# BBQ_Blower.net
KiCad netlist of a schematic drawn in EAGLE
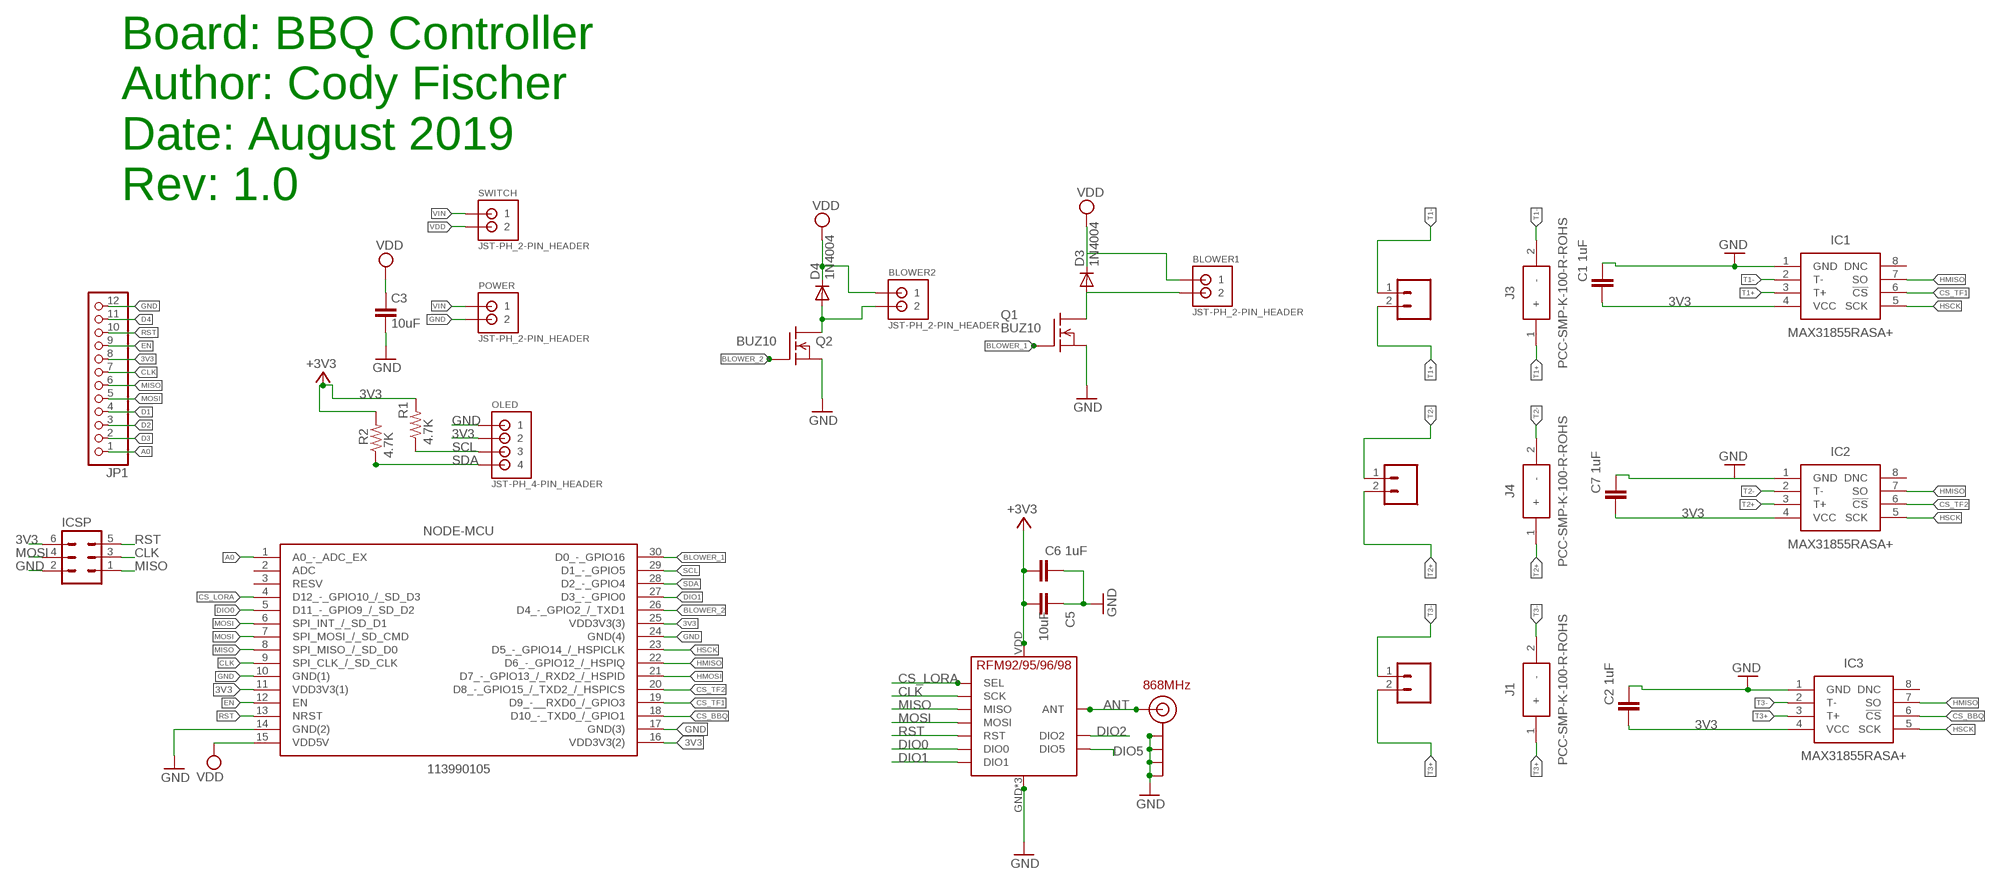
[diagram p0: schematic, sheet 1]

(export (version "E")
  (design (tool "Eeschema 10.0.6"))
  (components
    (comp (ref "BLOWER1")
      (value "JST-PH_2-PIN_HEADER")
      (footprint "eagle-import:JST_B2B-PH_HEADER")
      (libsource (lib "eagle-import") (part "JST-PH_2-PIN_HEADER"))
    )
    (comp (ref "BLOWER2")
      (value "JST-PH_2-PIN_HEADER")
      (footprint "eagle-import:JST_B2B-PH_HEADER")
      (libsource (lib "eagle-import") (part "JST-PH_2-PIN_HEADER"))
    )
    (comp (ref "C1")
      (value "1uF")
      (footprint "eagle-import:C0805K")
      (libsource (lib "eagle-import") (part "C-EUC0805K"))
    )
    (comp (ref "C2")
      (value "1uF")
      (footprint "eagle-import:C0805K")
      (libsource (lib "eagle-import") (part "C-EUC0805K"))
    )
    (comp (ref "C3")
      (value "10uF")
      (footprint "eagle-import:C025-050X050")
      (libsource (lib "eagle-import") (part "C-EU025-050X050"))
    )
    (comp (ref "C5")
      (value "10uF")
      (footprint "eagle-import:C0805K")
      (libsource (lib "eagle-import") (part "C-EUC0805K"))
    )
    (comp (ref "C6")
      (value "1uF")
      (footprint "eagle-import:C0805K")
      (libsource (lib "eagle-import") (part "C-EUC0805K"))
    )
    (comp (ref "C7")
      (value "1uF")
      (footprint "eagle-import:C0805K")
      (libsource (lib "eagle-import") (part "C-EUC0805K"))
    )
    (comp (ref "D3")
      (value "1N4004")
      (footprint "eagle-import:DO41-10")
      (libsource (lib "eagle-import") (part "1N4004"))
    )
    (comp (ref "D4")
      (value "1N4004")
      (footprint "eagle-import:DO41-10")
      (libsource (lib "eagle-import") (part "1N4004"))
    )
    (comp (ref "IC1")
      (value "MAX31855RASA+")
      (footprint "eagle-import:SOIC127P600X175-8N")
      (fields (field (name "RS_PART_NUMBER") "7833891P"))
      (libsource (lib "eagle-import") (part "MAX31855RASA+"))
    )
    (comp (ref "IC2")
      (value "MAX31855RASA+")
      (footprint "eagle-import:SOIC127P600X175-8N")
      (fields (field (name "RS_PART_NUMBER") "7833891P"))
      (libsource (lib "eagle-import") (part "MAX31855RASA+"))
    )
    (comp (ref "IC3")
      (value "MAX31855RASA+")
      (footprint "eagle-import:SOIC127P600X175-8N")
      (fields (field (name "RS_PART_NUMBER") "7833891P"))
      (libsource (lib "eagle-import") (part "MAX31855RASA+"))
    )
    (comp (ref "ICSP")
      (value "MA03-2")
      (footprint "eagle-import:MA03-2")
      (libsource (lib "eagle-import") (part "MA03-2"))
    )
    (comp (ref "J$2")
      (value "ANTENNATINY")
      (footprint "eagle-import:SMA_UFL_PAD_TINY")
      (libsource (lib "eagle-import") (part "ANTENNATINY"))
    )
    (comp (ref "J1")
      (value "PCC-SMP-K-100-R-ROHS")
      (footprint "eagle-import:PCC-SMP")
      (libsource (lib "eagle-import") (part "PCC-SMP-K-100-R-ROHS"))
    )
    (comp (ref "J3")
      (value "PCC-SMP-K-100-R-ROHS")
      (footprint "eagle-import:PCC-SMP")
      (libsource (lib "eagle-import") (part "PCC-SMP-K-100-R-ROHS"))
    )
    (comp (ref "J4")
      (value "PCC-SMP-K-100-R-ROHS")
      (footprint "eagle-import:PCC-SMP")
      (libsource (lib "eagle-import") (part "PCC-SMP-K-100-R-ROHS"))
    )
    (comp (ref "JP1")
      (value "PINHD-1X12")
      (footprint "eagle-import:1X12")
      (libsource (lib "eagle-import") (part "PINHD-1X12"))
    )
    (comp (ref "NODE-MCU")
      (value "113990105")
      (footprint "eagle-import:DIP2286W64P254L4826H735Q30N")
      (libsource (lib "eagle-import") (part "113990105"))
    )
    (comp (ref "OLED")
      (value "JST-PH_4-PIN_HEADER")
      (footprint "eagle-import:JST_B4B-PH_HEADER")
      (libsource (lib "eagle-import") (part "JST-PH_4-PIN_HEADER"))
    )
    (comp (ref "POWER")
      (value "JST-PH_2-PIN_HEADER")
      (footprint "eagle-import:JST_B2B-PH_HEADER")
      (libsource (lib "eagle-import") (part "JST-PH_2-PIN_HEADER"))
    )
    (comp (ref "Q1")
      (value "BUZ10")
      (footprint "eagle-import:TO220")
      (libsource (lib "eagle-import") (part "BUZ10"))
    )
    (comp (ref "Q2")
      (value "BUZ10")
      (footprint "eagle-import:TO220")
      (libsource (lib "eagle-import") (part "BUZ10"))
    )
    (comp (ref "R1")
      (value "4.7K")
      (footprint "eagle-import:0805-RES")
      (libsource (lib "eagle-import") (part "RESISTOR0805-RES"))
    )
    (comp (ref "R2")
      (value "4.7K")
      (footprint "eagle-import:0805-RES")
      (libsource (lib "eagle-import") (part "RESISTOR0805-RES"))
    )
    (comp (ref "SWITCH")
      (value "JST-PH_2-PIN_HEADER")
      (footprint "eagle-import:JST_B2B-PH_HEADER")
      (libsource (lib "eagle-import") (part "JST-PH_2-PIN_HEADER"))
    )
    (comp (ref "TH1")
      (value "CONN_025MM")
      (footprint "eagle-import:SCREWTERMINAL-5MM-2")
      (libsource (lib "eagle-import") (part "CONN_025MM"))
    )
    (comp (ref "TH2")
      (value "CONN_025MM")
      (footprint "eagle-import:SCREWTERMINAL-5MM-2")
      (libsource (lib "eagle-import") (part "CONN_025MM"))
    )
    (comp (ref "TH3")
      (value "CONN_025MM")
      (footprint "eagle-import:SCREWTERMINAL-5MM-2")
      (libsource (lib "eagle-import") (part "CONN_025MM"))
    )
    (comp (ref "U$5")
      (value "RFM95")
      (footprint "eagle-import:RFM95")
      (libsource (lib "eagle-import") (part "RFM95"))
    )
  )
  (nets
    (net (code "1") (name "/ANT") (class "Default")
      (node (ref "J$2") (pin "ANT1") (pinfunction "SIGNAL_ANT1") (pintype "bidirectional"))
      (node (ref "J$2") (pin "ANT2") (pinfunction "SIGNAL_ANT2") (pintype "bidirectional"))
      (node (ref "J$2") (pin "ANT3") (pinfunction "SIGNAL_ANT3") (pintype "bidirectional"))
      (node (ref "U$5") (pin "ANT") (pinfunction "ANT_ANT") (pintype "passive"))
    )
    (net (code "2") (name "/DIO2") (class "Default")
      (node (ref "U$5") (pin "DIO2") (pinfunction "DIO2_DIO2") (pintype "open_collector"))
    )
    (net (code "3") (name "/DIO5") (class "Default")
      (node (ref "U$5") (pin "DIO5") (pinfunction "DIO5_DIO5") (pintype "open_collector"))
    )
    (net (code "4") (name "3V3") (class "Default")
      (node (ref "C1") (pin "2") (pinfunction "2_2") (pintype "passive"))
      (node (ref "C2") (pin "2") (pinfunction "2_2") (pintype "passive"))
      (node (ref "C5") (pin "2") (pinfunction "2_2") (pintype "passive"))
      (node (ref "C6") (pin "2") (pinfunction "2_2") (pintype "passive"))
      (node (ref "C7") (pin "2") (pinfunction "2_2") (pintype "passive"))
      (node (ref "IC1") (pin "4") (pinfunction "VCC_4") (pintype "power_in"))
      (node (ref "IC2") (pin "4") (pinfunction "VCC_4") (pintype "power_in"))
      (node (ref "IC3") (pin "4") (pinfunction "VCC_4") (pintype "power_in"))
      (node (ref "ICSP") (pin "6") (pinfunction "6_6") (pintype "passive"))
      (node (ref "JP1") (pin "8") (pinfunction "8_8") (pintype "passive"))
      (node (ref "NODE-MCU") (pin "11") (pinfunction "VDD3V3(1)_11") (pintype "power_in"))
      (node (ref "NODE-MCU") (pin "16") (pinfunction "VDD3V3(2)_16") (pintype "power_in"))
      (node (ref "NODE-MCU") (pin "25") (pinfunction "VDD3V3(3)_25") (pintype "power_in"))
      (node (ref "OLED") (pin "P2") (pinfunction "2_P2") (pintype "bidirectional"))
      (node (ref "R1") (pin "2") (pinfunction "2_2") (pintype "passive"))
      (node (ref "R2") (pin "2") (pinfunction "2_2") (pintype "passive"))
      (node (ref "U$5") (pin "VDD") (pinfunction "VCC_VDD") (pintype "power_in"))
    )
    (net (code "5") (name "A0") (class "Default")
      (node (ref "JP1") (pin "1") (pinfunction "1_1") (pintype "passive"))
      (node (ref "NODE-MCU") (pin "1") (pinfunction "A0_-_ADC_EX_1") (pintype "bidirectional"))
    )
    (net (code "6") (name "BLOWER_1") (class "Default")
      (node (ref "NODE-MCU") (pin "30") (pinfunction "D0_-_GPIO16_30") (pintype "bidirectional"))
      (node (ref "Q1") (pin "1") (pinfunction "G_1") (pintype "passive"))
    )
    (net (code "7") (name "BLOWER_2") (class "Default")
      (node (ref "NODE-MCU") (pin "26") (pinfunction "D4_-_GPIO2_/_TXD1_26") (pintype "bidirectional"))
      (node (ref "Q2") (pin "1") (pinfunction "G_1") (pintype "passive"))
    )
    (net (code "8") (name "CLK") (class "Default")
      (node (ref "ICSP") (pin "3") (pinfunction "3_3") (pintype "passive"))
      (node (ref "JP1") (pin "7") (pinfunction "7_7") (pintype "passive"))
      (node (ref "NODE-MCU") (pin "9") (pinfunction "SPI_CLK_/_SD_CLK_9") (pintype "bidirectional"))
      (node (ref "U$5") (pin "SCK") (pinfunction "SCK_SCK") (pintype "input"))
    )
    (net (code "9") (name "CS_BBQ") (class "Default")
      (node (ref "IC3") (pin "6") (pinfunction "~{CS}_6") (pintype "input"))
      (node (ref "NODE-MCU") (pin "18") (pinfunction "D10_-_TXD0_/_GPIO1_18") (pintype "bidirectional"))
    )
    (net (code "10") (name "CS_LORA") (class "Default")
      (node (ref "NODE-MCU") (pin "4") (pinfunction "D12_-_GPIO10_/_SD_D3_4") (pintype "bidirectional"))
      (node (ref "U$5") (pin "NSS") (pinfunction "SEL_NSS") (pintype "input"))
    )
    (net (code "11") (name "CS_TF1") (class "Default")
      (node (ref "IC1") (pin "6") (pinfunction "~{CS}_6") (pintype "input"))
      (node (ref "NODE-MCU") (pin "19") (pinfunction "D9_-__RXD0_/_GPIO3_19") (pintype "bidirectional"))
    )
    (net (code "12") (name "CS_TF2") (class "Default")
      (node (ref "IC2") (pin "6") (pinfunction "~{CS}_6") (pintype "input"))
      (node (ref "NODE-MCU") (pin "20") (pinfunction "D8_-_GPIO15_/_TXD2_/_HSPICS_20") (pintype "bidirectional"))
    )
    (net (code "13") (name "D1") (class "Default")
      (node (ref "JP1") (pin "4") (pinfunction "4_4") (pintype "passive"))
    )
    (net (code "14") (name "D2") (class "Default")
      (node (ref "JP1") (pin "3") (pinfunction "3_3") (pintype "passive"))
    )
    (net (code "15") (name "D3") (class "Default")
      (node (ref "JP1") (pin "2") (pinfunction "2_2") (pintype "passive"))
    )
    (net (code "16") (name "D4") (class "Default")
      (node (ref "JP1") (pin "11") (pinfunction "11_11") (pintype "passive"))
    )
    (net (code "17") (name "DIO0") (class "Default")
      (node (ref "NODE-MCU") (pin "5") (pinfunction "D11_-_GPIO9_/_SD_D2_5") (pintype "bidirectional"))
      (node (ref "U$5") (pin "DIO0") (pinfunction "DIO0_DIO0") (pintype "open_collector"))
    )
    (net (code "18") (name "DIO1") (class "Default")
      (node (ref "NODE-MCU") (pin "27") (pinfunction "D3_-_GPIO0_27") (pintype "bidirectional"))
      (node (ref "U$5") (pin "DIO1") (pinfunction "DIO1_DIO1") (pintype "open_collector"))
    )
    (net (code "19") (name "EN") (class "Default")
      (node (ref "JP1") (pin "9") (pinfunction "9_9") (pintype "passive"))
      (node (ref "NODE-MCU") (pin "12") (pinfunction "EN_12") (pintype "input"))
    )
    (net (code "20") (name "GND") (class "Default")
      (node (ref "C1") (pin "1") (pinfunction "1_1") (pintype "passive"))
      (node (ref "C2") (pin "1") (pinfunction "1_1") (pintype "passive"))
      (node (ref "C3") (pin "2") (pinfunction "2_2") (pintype "passive"))
      (node (ref "C5") (pin "1") (pinfunction "1_1") (pintype "passive"))
      (node (ref "C6") (pin "1") (pinfunction "1_1") (pintype "passive"))
      (node (ref "C7") (pin "1") (pinfunction "1_1") (pintype "passive"))
      (node (ref "IC1") (pin "1") (pinfunction "GND_1") (pintype "power_in"))
      (node (ref "IC2") (pin "1") (pinfunction "GND_1") (pintype "power_in"))
      (node (ref "IC3") (pin "1") (pinfunction "GND_1") (pintype "power_in"))
      (node (ref "ICSP") (pin "2") (pinfunction "2_2") (pintype "passive"))
      (node (ref "J$2") (pin "GND1") (pinfunction "GND_GND1") (pintype "bidirectional"))
      (node (ref "J$2") (pin "GND2") (pinfunction "GND_GND2") (pintype "bidirectional"))
      (node (ref "J$2") (pin "GND3") (pinfunction "GND_GND3") (pintype "bidirectional"))
      (node (ref "J$2") (pin "GND4") (pinfunction "GND_GND4") (pintype "bidirectional"))
      (node (ref "JP1") (pin "12") (pinfunction "12_12") (pintype "passive"))
      (node (ref "NODE-MCU") (pin "10") (pinfunction "GND(1)_10") (pintype "power_in"))
      (node (ref "NODE-MCU") (pin "14") (pinfunction "GND(2)_14") (pintype "power_in"))
      (node (ref "NODE-MCU") (pin "17") (pinfunction "GND(3)_17") (pintype "power_in"))
      (node (ref "NODE-MCU") (pin "24") (pinfunction "GND(4)_24") (pintype "power_in"))
      (node (ref "OLED") (pin "P1") (pinfunction "1_P1") (pintype "bidirectional"))
      (node (ref "POWER") (pin "P2") (pinfunction "2_P2") (pintype "bidirectional"))
      (node (ref "Q1") (pin "3") (pinfunction "S_3") (pintype "passive"))
      (node (ref "Q2") (pin "3") (pinfunction "S_3") (pintype "passive"))
      (node (ref "U$5") (pin "GND") (pinfunction "GND_GND") (pintype "power_in"))
      (node (ref "U$5") (pin "GND1") (pinfunction "GND_GND1") (pintype "power_in"))
      (node (ref "U$5") (pin "GND2") (pinfunction "GND_GND2") (pintype "power_in"))
    )
    (net (code "21") (name "HMISO") (class "Default")
      (node (ref "IC1") (pin "7") (pinfunction "SO_7") (pintype "output"))
      (node (ref "IC2") (pin "7") (pinfunction "SO_7") (pintype "output"))
      (node (ref "IC3") (pin "7") (pinfunction "SO_7") (pintype "output"))
      (node (ref "NODE-MCU") (pin "22") (pinfunction "D6_-_GPIO12_/_HSPIQ_22") (pintype "bidirectional"))
    )
    (net (code "22") (name "HMOSI") (class "Default")
      (node (ref "NODE-MCU") (pin "21") (pinfunction "D7_-_GPIO13_/_RXD2_/_HSPID_21") (pintype "bidirectional"))
    )
    (net (code "23") (name "HSCK") (class "Default")
      (node (ref "IC1") (pin "5") (pinfunction "SCK_5") (pintype "input"))
      (node (ref "IC2") (pin "5") (pinfunction "SCK_5") (pintype "input"))
      (node (ref "IC3") (pin "5") (pinfunction "SCK_5") (pintype "input"))
      (node (ref "NODE-MCU") (pin "23") (pinfunction "D5_-_GPIO14_/_HSPICLK_23") (pintype "bidirectional"))
    )
    (net (code "24") (name "MISO") (class "Default")
      (node (ref "ICSP") (pin "1") (pinfunction "1_1") (pintype "passive"))
      (node (ref "JP1") (pin "6") (pinfunction "6_6") (pintype "passive"))
      (node (ref "NODE-MCU") (pin "8") (pinfunction "SPI_MISO_/_SD_D0_8") (pintype "bidirectional"))
      (node (ref "U$5") (pin "MISO") (pinfunction "MISO_MISO") (pintype "input"))
    )
    (net (code "25") (name "MOSI") (class "Default")
      (node (ref "ICSP") (pin "4") (pinfunction "4_4") (pintype "passive"))
      (node (ref "JP1") (pin "5") (pinfunction "5_5") (pintype "passive"))
      (node (ref "NODE-MCU") (pin "6") (pinfunction "SPI_INT_/_SD_D1_6") (pintype "bidirectional"))
      (node (ref "NODE-MCU") (pin "7") (pinfunction "SPI_MOSI_/_SD_CMD_7") (pintype "bidirectional"))
      (node (ref "U$5") (pin "MOSI") (pinfunction "MOSI_MOSI") (pintype "output"))
    )
    (net (code "26") (name "Net-(BLOWER1-2)") (class "Default")
      (node (ref "BLOWER1") (pin "P2") (pinfunction "2_P2") (pintype "bidirectional"))
      (node (ref "D3") (pin "A") (pinfunction "A_A") (pintype "passive"))
      (node (ref "Q1") (pin "2") (pinfunction "D_2") (pintype "passive"))
    )
    (net (code "27") (name "Net-(BLOWER2-2)") (class "Default")
      (node (ref "BLOWER2") (pin "P2") (pinfunction "2_P2") (pintype "bidirectional"))
      (node (ref "D4") (pin "A") (pinfunction "A_A") (pintype "passive"))
      (node (ref "Q2") (pin "2") (pinfunction "D_2") (pintype "passive"))
    )
    (net (code "28") (name "RST") (class "Default")
      (node (ref "ICSP") (pin "5") (pinfunction "5_5") (pintype "passive"))
      (node (ref "JP1") (pin "10") (pinfunction "10_10") (pintype "passive"))
      (node (ref "NODE-MCU") (pin "13") (pinfunction "NRST_13") (pintype "input"))
      (node (ref "U$5") (pin "RST") (pinfunction "RST_RST") (pintype "open_collector"))
    )
    (net (code "29") (name "SCL") (class "Default")
      (node (ref "NODE-MCU") (pin "29") (pinfunction "D1_-_GPIO5_29") (pintype "bidirectional"))
      (node (ref "OLED") (pin "P3") (pinfunction "3_P3") (pintype "bidirectional"))
      (node (ref "R1") (pin "1") (pinfunction "1_1") (pintype "passive"))
    )
    (net (code "30") (name "SDA") (class "Default")
      (node (ref "NODE-MCU") (pin "28") (pinfunction "D2_-_GPIO4_28") (pintype "bidirectional"))
      (node (ref "OLED") (pin "P4") (pinfunction "4_P4") (pintype "bidirectional"))
      (node (ref "R2") (pin "1") (pinfunction "1_1") (pintype "passive"))
    )
    (net (code "31") (name "T1+") (class "Default")
      (node (ref "IC1") (pin "3") (pinfunction "T+_3") (pintype "input"))
      (node (ref "J3") (pin "1") (pinfunction "+_1") (pintype "passive"))
      (node (ref "TH3") (pin "2") (pinfunction "2_2") (pintype "passive"))
    )
    (net (code "32") (name "T1-") (class "Default")
      (node (ref "IC1") (pin "2") (pinfunction "T-_2") (pintype "input"))
      (node (ref "J3") (pin "2") (pinfunction "-_2") (pintype "passive"))
      (node (ref "TH3") (pin "1") (pinfunction "1_1") (pintype "passive"))
    )
    (net (code "33") (name "T2+") (class "Default")
      (node (ref "IC2") (pin "3") (pinfunction "T+_3") (pintype "input"))
      (node (ref "J4") (pin "1") (pinfunction "+_1") (pintype "passive"))
      (node (ref "TH2") (pin "2") (pinfunction "2_2") (pintype "passive"))
    )
    (net (code "34") (name "T2-") (class "Default")
      (node (ref "IC2") (pin "2") (pinfunction "T-_2") (pintype "input"))
      (node (ref "J4") (pin "2") (pinfunction "-_2") (pintype "passive"))
      (node (ref "TH2") (pin "1") (pinfunction "1_1") (pintype "passive"))
    )
    (net (code "35") (name "T3+") (class "Default")
      (node (ref "IC3") (pin "3") (pinfunction "T+_3") (pintype "input"))
      (node (ref "J1") (pin "1") (pinfunction "+_1") (pintype "passive"))
      (node (ref "TH1") (pin "2") (pinfunction "2_2") (pintype "passive"))
    )
    (net (code "36") (name "T3-") (class "Default")
      (node (ref "IC3") (pin "2") (pinfunction "T-_2") (pintype "input"))
      (node (ref "J1") (pin "2") (pinfunction "-_2") (pintype "passive"))
      (node (ref "TH1") (pin "1") (pinfunction "1_1") (pintype "passive"))
    )
    (net (code "37") (name "VDD") (class "Default")
      (node (ref "BLOWER1") (pin "P1") (pinfunction "1_P1") (pintype "bidirectional"))
      (node (ref "BLOWER2") (pin "P1") (pinfunction "1_P1") (pintype "bidirectional"))
      (node (ref "C3") (pin "1") (pinfunction "1_1") (pintype "passive"))
      (node (ref "D3") (pin "C") (pinfunction "C_C") (pintype "passive"))
      (node (ref "D4") (pin "C") (pinfunction "C_C") (pintype "passive"))
      (node (ref "NODE-MCU") (pin "15") (pinfunction "VDD5V_15") (pintype "power_in"))
      (node (ref "SWITCH") (pin "P2") (pinfunction "2_P2") (pintype "bidirectional"))
    )
    (net (code "38") (name "VIN") (class "Default")
      (node (ref "POWER") (pin "P1") (pinfunction "1_P1") (pintype "bidirectional"))
      (node (ref "SWITCH") (pin "P1") (pinfunction "1_P1") (pintype "bidirectional"))
    )
    (net (code "39") (name "unconnected-(IC1-DNC-Pad8)") (class "Default")
      (node (ref "IC1") (pin "8") (pinfunction "DNC_8") (pintype "passive"))
    )
    (net (code "40") (name "unconnected-(IC2-DNC-Pad8)") (class "Default")
      (node (ref "IC2") (pin "8") (pinfunction "DNC_8") (pintype "passive"))
    )
    (net (code "41") (name "unconnected-(IC3-DNC-Pad8)") (class "Default")
      (node (ref "IC3") (pin "8") (pinfunction "DNC_8") (pintype "passive"))
    )
    (net (code "42") (name "unconnected-(NODE-MCU-ADC-Pad2)") (class "Default")
      (node (ref "NODE-MCU") (pin "2") (pinfunction "ADC_2") (pintype "bidirectional"))
    )
    (net (code "43") (name "unconnected-(NODE-MCU-RESV-Pad3)") (class "Default")
      (node (ref "NODE-MCU") (pin "3") (pinfunction "RESV_3") (pintype "passive"))
    )
  )
)
